# STM32_PWM.net
KiCad netlist of a schematic drawn in Altium Designer
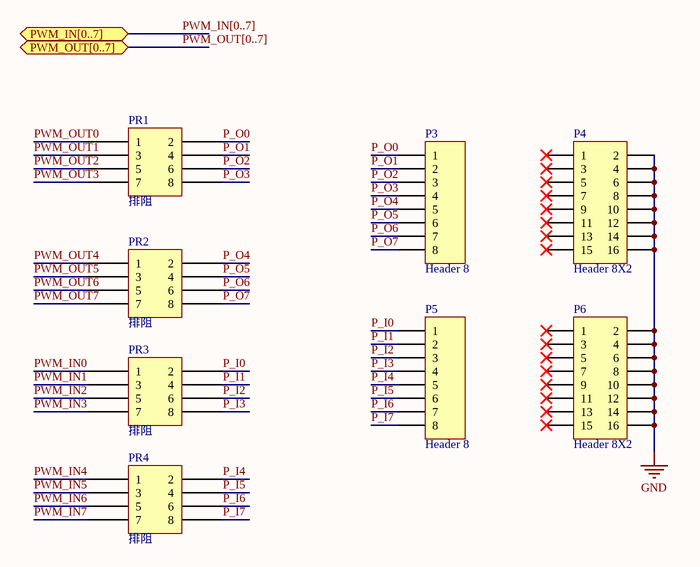
[diagram p0: STM32_PWM.SchDoc]

(export (version "E")
  (design (tool "Eeschema 10.0.6"))
  (components
    (comp (ref "P3")
      (value "Header 8")
      (footprint "HDR1X8")
      (description "Header, 8-Pin")
      (fields (field (name "PUBLISHER") "Altium Limited"))
      (libsource (lib "Miscellaneous Connectors") (part "Header 8"))
    )
    (comp (ref "P4")
      (value "Header 8X2")
      (footprint "HDR2X8")
      (description "Header, 8-Pin, Dual row")
      (fields (field (name "PUBLISHER") "Altium Limited"))
      (libsource (lib "Miscellaneous Connectors") (part "Header 8X2"))
    )
    (comp (ref "P5")
      (value "Header 8")
      (footprint "HDR1X8")
      (description "Header, 8-Pin")
      (fields (field (name "PUBLISHER") "Altium Limited"))
      (libsource (lib "Miscellaneous Connectors") (part "Header 8"))
    )
    (comp (ref "P6")
      (value "Header 8X2")
      (footprint "HDR2X8")
      (description "Header, 8-Pin, Dual row")
      (fields (field (name "PUBLISHER") "Altium Limited"))
      (libsource (lib "Miscellaneous Connectors") (part "Header 8X2"))
    )
    (comp (ref "PR1") (value "排阻") (footprint "8P4R-0603") (libsource (lib "Schlib1") (part "RES*4")))
    (comp (ref "PR2") (value "排阻") (footprint "8P4R-0603") (libsource (lib "Schlib1") (part "RES*4")))
    (comp (ref "PR3") (value "排阻") (footprint "8P4R-0603") (libsource (lib "Schlib1") (part "RES*4")))
    (comp (ref "PR4") (value "排阻") (footprint "8P4R-0603") (libsource (lib "Schlib1") (part "RES*4")))
  )
  (nets
    (net (code "1") (name "/PWM_IN0") (class "Default")
      (node (ref "PR3") (pin "1") (pinfunction "1_1") (pintype "passive"))
    )
    (net (code "2") (name "/PWM_IN1") (class "Default")
      (node (ref "PR3") (pin "3") (pinfunction "3_3") (pintype "passive"))
    )
    (net (code "3") (name "/PWM_IN2") (class "Default")
      (node (ref "PR3") (pin "5") (pinfunction "5_5") (pintype "passive"))
    )
    (net (code "4") (name "/PWM_IN3") (class "Default")
      (node (ref "PR3") (pin "7") (pinfunction "7_7") (pintype "passive"))
    )
    (net (code "5") (name "/PWM_IN4") (class "Default")
      (node (ref "PR4") (pin "1") (pinfunction "1_1") (pintype "passive"))
    )
    (net (code "6") (name "/PWM_IN5") (class "Default")
      (node (ref "PR4") (pin "3") (pinfunction "3_3") (pintype "passive"))
    )
    (net (code "7") (name "/PWM_IN6") (class "Default")
      (node (ref "PR4") (pin "5") (pinfunction "5_5") (pintype "passive"))
    )
    (net (code "8") (name "/PWM_IN7") (class "Default")
      (node (ref "PR4") (pin "7") (pinfunction "7_7") (pintype "passive"))
    )
    (net (code "10") (name "/PWM_OUT0") (class "Default")
      (node (ref "PR1") (pin "1") (pinfunction "1_1") (pintype "passive"))
    )
    (net (code "11") (name "/PWM_OUT1") (class "Default")
      (node (ref "PR1") (pin "3") (pinfunction "3_3") (pintype "passive"))
    )
    (net (code "12") (name "/PWM_OUT2") (class "Default")
      (node (ref "PR1") (pin "5") (pinfunction "5_5") (pintype "passive"))
    )
    (net (code "13") (name "/PWM_OUT3") (class "Default")
      (node (ref "PR1") (pin "7") (pinfunction "7_7") (pintype "passive"))
    )
    (net (code "14") (name "/PWM_OUT4") (class "Default")
      (node (ref "PR2") (pin "1") (pinfunction "1_1") (pintype "passive"))
    )
    (net (code "15") (name "/PWM_OUT5") (class "Default")
      (node (ref "PR2") (pin "3") (pinfunction "3_3") (pintype "passive"))
    )
    (net (code "16") (name "/PWM_OUT6") (class "Default")
      (node (ref "PR2") (pin "5") (pinfunction "5_5") (pintype "passive"))
    )
    (net (code "17") (name "/PWM_OUT7") (class "Default")
      (node (ref "PR2") (pin "7") (pinfunction "7_7") (pintype "passive"))
    )
    (net (code "19") (name "/P_I0") (class "Default")
      (node (ref "P5") (pin "1") (pinfunction "1_1") (pintype "passive"))
      (node (ref "PR3") (pin "2") (pinfunction "2_2") (pintype "passive"))
    )
    (net (code "20") (name "/P_I1") (class "Default")
      (node (ref "P5") (pin "2") (pinfunction "2_2") (pintype "passive"))
      (node (ref "PR3") (pin "4") (pinfunction "4_4") (pintype "passive"))
    )
    (net (code "21") (name "/P_I2") (class "Default")
      (node (ref "P5") (pin "3") (pinfunction "3_3") (pintype "passive"))
      (node (ref "PR3") (pin "6") (pinfunction "6_6") (pintype "passive"))
    )
    (net (code "22") (name "/P_I3") (class "Default")
      (node (ref "P5") (pin "4") (pinfunction "4_4") (pintype "passive"))
      (node (ref "PR3") (pin "8") (pinfunction "8_8") (pintype "passive"))
    )
    (net (code "23") (name "/P_I4") (class "Default")
      (node (ref "P5") (pin "5") (pinfunction "5_5") (pintype "passive"))
      (node (ref "PR4") (pin "2") (pinfunction "2_2") (pintype "passive"))
    )
    (net (code "24") (name "/P_I5") (class "Default")
      (node (ref "P5") (pin "6") (pinfunction "6_6") (pintype "passive"))
      (node (ref "PR4") (pin "4") (pinfunction "4_4") (pintype "passive"))
    )
    (net (code "25") (name "/P_I6") (class "Default")
      (node (ref "P5") (pin "7") (pinfunction "7_7") (pintype "passive"))
      (node (ref "PR4") (pin "6") (pinfunction "6_6") (pintype "passive"))
    )
    (net (code "26") (name "/P_I7") (class "Default")
      (node (ref "P5") (pin "8") (pinfunction "8_8") (pintype "passive"))
      (node (ref "PR4") (pin "8") (pinfunction "8_8") (pintype "passive"))
    )
    (net (code "27") (name "/P_O0") (class "Default")
      (node (ref "P3") (pin "1") (pinfunction "1_1") (pintype "passive"))
      (node (ref "PR1") (pin "2") (pinfunction "2_2") (pintype "passive"))
    )
    (net (code "28") (name "/P_O1") (class "Default")
      (node (ref "P3") (pin "2") (pinfunction "2_2") (pintype "passive"))
      (node (ref "PR1") (pin "4") (pinfunction "4_4") (pintype "passive"))
    )
    (net (code "29") (name "/P_O2") (class "Default")
      (node (ref "P3") (pin "3") (pinfunction "3_3") (pintype "passive"))
      (node (ref "PR1") (pin "6") (pinfunction "6_6") (pintype "passive"))
    )
    (net (code "30") (name "/P_O3") (class "Default")
      (node (ref "P3") (pin "4") (pinfunction "4_4") (pintype "passive"))
      (node (ref "PR1") (pin "8") (pinfunction "8_8") (pintype "passive"))
    )
    (net (code "31") (name "/P_O4") (class "Default")
      (node (ref "P3") (pin "5") (pinfunction "5_5") (pintype "passive"))
      (node (ref "PR2") (pin "2") (pinfunction "2_2") (pintype "passive"))
    )
    (net (code "32") (name "/P_O5") (class "Default")
      (node (ref "P3") (pin "6") (pinfunction "6_6") (pintype "passive"))
      (node (ref "PR2") (pin "4") (pinfunction "4_4") (pintype "passive"))
    )
    (net (code "33") (name "/P_O6") (class "Default")
      (node (ref "P3") (pin "7") (pinfunction "7_7") (pintype "passive"))
      (node (ref "PR2") (pin "6") (pinfunction "6_6") (pintype "passive"))
    )
    (net (code "34") (name "/P_O7") (class "Default")
      (node (ref "P3") (pin "8") (pinfunction "8_8") (pintype "passive"))
      (node (ref "PR2") (pin "8") (pinfunction "8_8") (pintype "passive"))
    )
    (net (code "35") (name "GND") (class "Default")
      (node (ref "P4") (pin "10") (pinfunction "10_10") (pintype "passive"))
      (node (ref "P4") (pin "12") (pinfunction "12_12") (pintype "passive"))
      (node (ref "P4") (pin "14") (pinfunction "14_14") (pintype "passive"))
      (node (ref "P4") (pin "16") (pinfunction "16_16") (pintype "passive"))
      (node (ref "P4") (pin "2") (pinfunction "2_2") (pintype "passive"))
      (node (ref "P4") (pin "4") (pinfunction "4_4") (pintype "passive"))
      (node (ref "P4") (pin "6") (pinfunction "6_6") (pintype "passive"))
      (node (ref "P4") (pin "8") (pinfunction "8_8") (pintype "passive"))
      (node (ref "P6") (pin "10") (pinfunction "10_10") (pintype "passive"))
      (node (ref "P6") (pin "12") (pinfunction "12_12") (pintype "passive"))
      (node (ref "P6") (pin "14") (pinfunction "14_14") (pintype "passive"))
      (node (ref "P6") (pin "16") (pinfunction "16_16") (pintype "passive"))
      (node (ref "P6") (pin "2") (pinfunction "2_2") (pintype "passive"))
      (node (ref "P6") (pin "4") (pinfunction "4_4") (pintype "passive"))
      (node (ref "P6") (pin "6") (pinfunction "6_6") (pintype "passive"))
      (node (ref "P6") (pin "8") (pinfunction "8_8") (pintype "passive"))
    )
    (net (code "36") (name "unconnected-(P4-Pad1)") (class "Default")
      (node (ref "P4") (pin "1") (pinfunction "1_1") (pintype "passive+no_connect"))
    )
    (net (code "37") (name "unconnected-(P4-Pad3)") (class "Default")
      (node (ref "P4") (pin "3") (pinfunction "3_3") (pintype "passive+no_connect"))
    )
    (net (code "38") (name "unconnected-(P4-Pad5)") (class "Default")
      (node (ref "P4") (pin "5") (pinfunction "5_5") (pintype "passive+no_connect"))
    )
    (net (code "39") (name "unconnected-(P4-Pad7)") (class "Default")
      (node (ref "P4") (pin "7") (pinfunction "7_7") (pintype "passive+no_connect"))
    )
    (net (code "40") (name "unconnected-(P4-Pad9)") (class "Default")
      (node (ref "P4") (pin "9") (pinfunction "9_9") (pintype "passive+no_connect"))
    )
    (net (code "41") (name "unconnected-(P4-Pad11)") (class "Default")
      (node (ref "P4") (pin "11") (pinfunction "11_11") (pintype "passive+no_connect"))
    )
    (net (code "42") (name "unconnected-(P4-Pad13)") (class "Default")
      (node (ref "P4") (pin "13") (pinfunction "13_13") (pintype "passive+no_connect"))
    )
    (net (code "43") (name "unconnected-(P4-Pad15)") (class "Default")
      (node (ref "P4") (pin "15") (pinfunction "15_15") (pintype "passive+no_connect"))
    )
    (net (code "44") (name "unconnected-(P6-Pad1)") (class "Default")
      (node (ref "P6") (pin "1") (pinfunction "1_1") (pintype "passive+no_connect"))
    )
    (net (code "45") (name "unconnected-(P6-Pad3)") (class "Default")
      (node (ref "P6") (pin "3") (pinfunction "3_3") (pintype "passive+no_connect"))
    )
    (net (code "46") (name "unconnected-(P6-Pad5)") (class "Default")
      (node (ref "P6") (pin "5") (pinfunction "5_5") (pintype "passive+no_connect"))
    )
    (net (code "47") (name "unconnected-(P6-Pad7)") (class "Default")
      (node (ref "P6") (pin "7") (pinfunction "7_7") (pintype "passive+no_connect"))
    )
    (net (code "48") (name "unconnected-(P6-Pad9)") (class "Default")
      (node (ref "P6") (pin "9") (pinfunction "9_9") (pintype "passive+no_connect"))
    )
    (net (code "49") (name "unconnected-(P6-Pad11)") (class "Default")
      (node (ref "P6") (pin "11") (pinfunction "11_11") (pintype "passive+no_connect"))
    )
    (net (code "50") (name "unconnected-(P6-Pad13)") (class "Default")
      (node (ref "P6") (pin "13") (pinfunction "13_13") (pintype "passive+no_connect"))
    )
    (net (code "51") (name "unconnected-(P6-Pad15)") (class "Default")
      (node (ref "P6") (pin "15") (pinfunction "15_15") (pintype "passive+no_connect"))
    )
  )
)
